# quadcopter.net
KiCad netlist of a schematic drawn in EAGLE
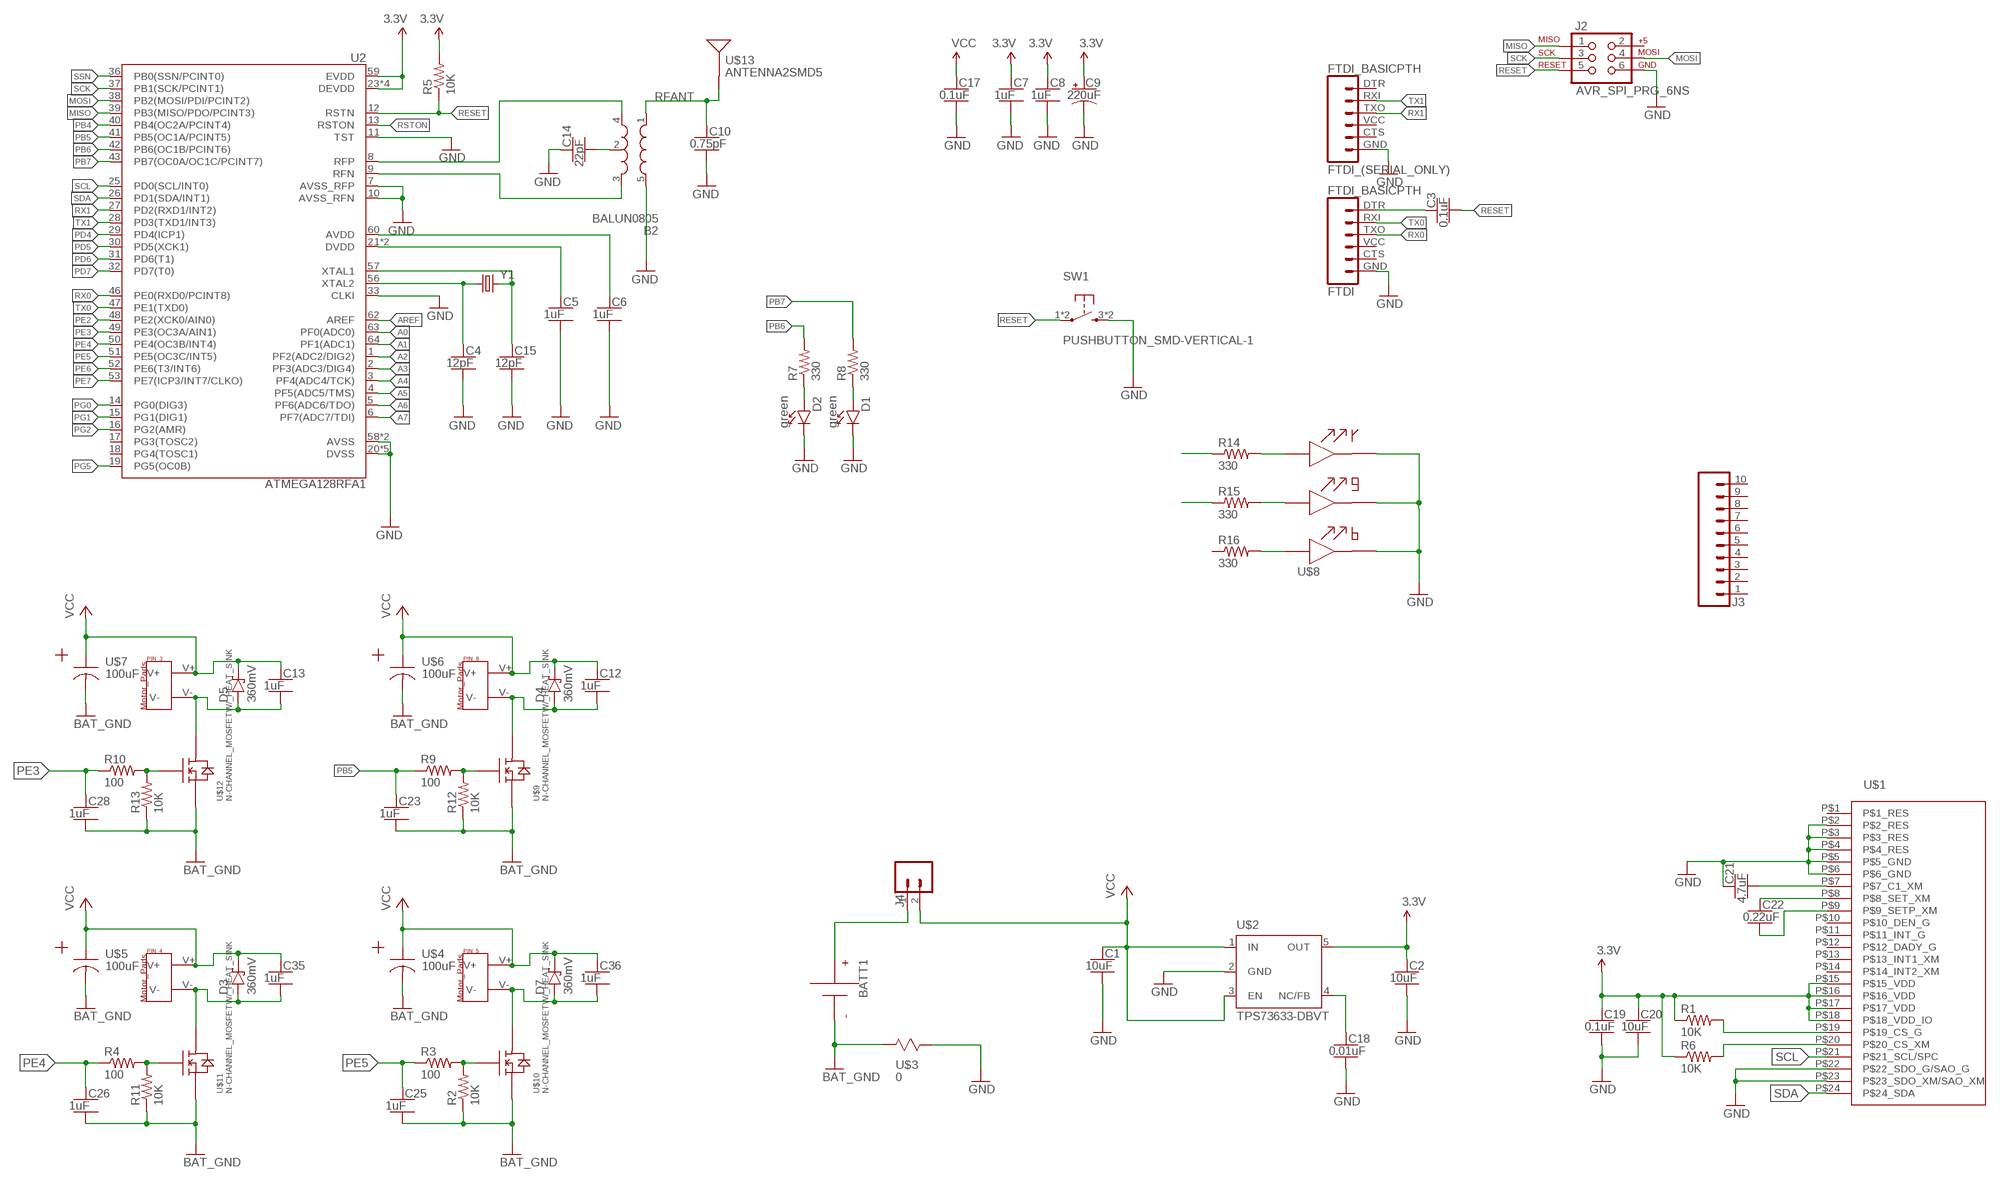
[diagram p0: schematic, sheet 1]

(export (version "E")
  (design (tool "Eeschema 10.0.6"))
  (components
    (comp (ref "B2")
      (value "BALUN0805")
      (footprint "eagle-import:BALUN")
      (fields (field (name "MFR") "Wurth Electronics Inc") (field (name "MPN") "748421245"))
      (libsource (lib "eagle-import") (part "BALUN0805"))
    )
    (comp (ref "BATT1")
      (value "BATTERY-HUBSAN-W/HOLDER")
      (footprint "eagle-import:BATTERY-W_HOLDER-380MAH-HUBSAN")
      (libsource (lib "eagle-import") (part "BATTERY-HUBSAN-W/HOLDER"))
    )
    (comp (ref "C1")
      (value "10uF")
      (footprint "eagle-import:CAPC2012X140_HS")
      (fields
        (field (name "MFR") "Murata Electronics North America")
        (field (name "MPN") "GRM21BR61E106KA73L")
      )
      (libsource (lib "eagle-import") (part "CAPACITOR-NP_SMD-2012-0805_CERAMIC-10UF"))
    )
    (comp (ref "C2")
      (value "10uF")
      (footprint "eagle-import:CAPC2012X140_HS")
      (fields
        (field (name "MFR") "Murata Electronics North America")
        (field (name "MPN") "GRM21BR61E106KA73L")
      )
      (libsource (lib "eagle-import") (part "CAPACITOR-NP_SMD-2012-0805_CERAMIC-10UF"))
    )
    (comp (ref "C3")
      (value "0.1uF")
      (footprint "eagle-import:CAPC2012X140_HS")
      (fields
        (field (name "MFR") "Murata Electronics North America")
        (field (name "MPN") "GRM21BR71H104KA01L")
      )
      (libsource (lib "eagle-import") (part "CAPACITOR-NP_SMD-2012-0805_CERAMIC-0.1UF"))
    )
    (comp (ref "C4")
      (value "12pF")
      (footprint "eagle-import:CAPC2012X140_HS")
      (fields
        (field (name "MFR") "Murata Electronics North America")
        (field (name "MPN") "GRM21A5C2E120JW01D")
      )
      (libsource (lib "eagle-import") (part "CAPACITOR-NP_SMD-2012-0805_CERAMIC-12PF"))
    )
    (comp (ref "C5")
      (value "1uF")
      (footprint "eagle-import:CAPC2012X140_HS")
      (fields
        (field (name "MFR") "Murata Electronics North America")
        (field (name "MPN") "GRM21BR71H105KA12L")
      )
      (libsource (lib "eagle-import") (part "CAPACITOR-NP_SMD-2012-0805_CERAMIC-1UF"))
    )
    (comp (ref "C6")
      (value "1uF")
      (footprint "eagle-import:CAPC2012X140_HS")
      (fields
        (field (name "MFR") "Murata Electronics North America")
        (field (name "MPN") "GRM21BR71H105KA12L")
      )
      (libsource (lib "eagle-import") (part "CAPACITOR-NP_SMD-2012-0805_CERAMIC-1UF"))
    )
    (comp (ref "C7")
      (value "1uF")
      (footprint "eagle-import:CAPC2012X140_HS")
      (fields
        (field (name "MFR") "Murata Electronics North America")
        (field (name "MPN") "GRM21BR71H105KA12L")
      )
      (libsource (lib "eagle-import") (part "CAPACITOR-NP_SMD-2012-0805_CERAMIC-1UF"))
    )
    (comp (ref "C8")
      (value "1uF")
      (footprint "eagle-import:CAPC2012X140_HS")
      (fields
        (field (name "MFR") "Murata Electronics North America")
        (field (name "MPN") "GRM21BR71H105KA12L")
      )
      (libsource (lib "eagle-import") (part "CAPACITOR-NP_SMD-2012-0805_CERAMIC-1UF"))
    )
    (comp (ref "C9")
      (value "220uF")
      (footprint "eagle-import:CAPMP7343X310_HS")
      (fields (field (name "MFR") "AVX Corporation") (field (name "MPN") "TAJD227K006RNJ"))
      (libsource (lib "eagle-import") (part "CAPACITOR-POL_SMD-7043-D_TANTALUM-220UF"))
    )
    (comp (ref "C10")
      (value "0.75pF")
      (footprint "eagle-import:CAPC2012X140_HS")
      (fields
        (field (name "MFR") "Murata Electronics North America")
        (field (name "MPN") "GQM2195C2AR75CB01D")
      )
      (libsource (lib "eagle-import") (part "CAPACITOR-NP_SMD-2012-0805_CERAMIC-0.75PF"))
    )
    (comp (ref "C12")
      (value "1uF")
      (footprint "eagle-import:CAPC2012X140_HS")
      (fields
        (field (name "MFR") "Murata Electronics North America")
        (field (name "MPN") "GRM21BR71H105KA12L")
      )
      (libsource (lib "eagle-import") (part "CAPACITOR-NP_SMD-2012-0805_CERAMIC-1UF"))
    )
    (comp (ref "C13")
      (value "1uF")
      (footprint "eagle-import:CAPC2012X140_HS")
      (fields
        (field (name "MFR") "Murata Electronics North America")
        (field (name "MPN") "GRM21BR71H105KA12L")
      )
      (libsource (lib "eagle-import") (part "CAPACITOR-NP_SMD-2012-0805_CERAMIC-1UF"))
    )
    (comp (ref "C14")
      (value "22pF")
      (footprint "eagle-import:CAPC2012X140_HS")
      (fields
        (field (name "MFR") "Murata Electronics North America")
        (field (name "MPN") "GRM21A5C2E220JW01D")
      )
      (libsource (lib "eagle-import") (part "CAPACITOR-NP_SMD-2012-0805_CERAMIC-22PF"))
    )
    (comp (ref "C15")
      (value "12pF")
      (footprint "eagle-import:CAPC2012X140_HS")
      (fields
        (field (name "MFR") "Murata Electronics North America")
        (field (name "MPN") "GRM21A5C2E120JW01D")
      )
      (libsource (lib "eagle-import") (part "CAPACITOR-NP_SMD-2012-0805_CERAMIC-12PF"))
    )
    (comp (ref "C17")
      (value "0.1uF")
      (footprint "eagle-import:CAPC2012X140_HS")
      (fields
        (field (name "MFR") "Murata Electronics North America")
        (field (name "MPN") "GRM21BR71H104KA01L")
      )
      (libsource (lib "eagle-import") (part "CAPACITOR-NP_SMD-2012-0805_CERAMIC-0.1UF"))
    )
    (comp (ref "C18")
      (value "0.01uF")
      (footprint "eagle-import:CAPC2012X140_HS")
      (fields
        (field (name "MFR") "Murata Electronics North America")
        (field (name "MPN") "GRM2195C1H103FA01D")
      )
      (libsource (lib "eagle-import") (part "CAPACITOR-NP_SMD-2012-0805_CERAMIC-0.01UF"))
    )
    (comp (ref "C19")
      (value "0.1uF")
      (footprint "eagle-import:CAPC2012X140_HS")
      (fields
        (field (name "MFR") "Murata Electronics North America")
        (field (name "MPN") "GRM21BR71H104KA01L")
      )
      (libsource (lib "eagle-import") (part "CAPACITOR-NP_SMD-2012-0805_CERAMIC-0.1UF"))
    )
    (comp (ref "C20")
      (value "10uF")
      (footprint "eagle-import:CAPC2012X140_HS")
      (fields
        (field (name "MFR") "Murata Electronics North America")
        (field (name "MPN") "GRM21BR61E106KA73L")
      )
      (libsource (lib "eagle-import") (part "CAPACITOR-NP_SMD-2012-0805_CERAMIC-10UF"))
    )
    (comp (ref "C21")
      (value "4.7uF")
      (footprint "eagle-import:CAPC2012X140_HS")
      (fields
        (field (name "MFR") "Murata Electronics North America")
        (field (name "MPN") "GRM21BR61E475KA12L")
      )
      (libsource (lib "eagle-import") (part "CAPACITOR-NP_SMD-2012-0805_CERAMIC-4.7UF"))
    )
    (comp (ref "C22")
      (value "0.22uF")
      (footprint "eagle-import:CAPC2012X140_HS")
      (fields
        (field (name "MFR") "Murata Electronics North America")
        (field (name "MPN") "GRM21BR71H224KA01L")
      )
      (libsource (lib "eagle-import") (part "CAPACITOR-NP_SMD-2012-0805_CERAMIC-0.22UF"))
    )
    (comp (ref "C23")
      (value "1uF")
      (footprint "eagle-import:CAPC2012X140_HS")
      (fields
        (field (name "MFR") "Murata Electronics North America")
        (field (name "MPN") "GRM21BR71H105KA12L")
      )
      (libsource (lib "eagle-import") (part "CAPACITOR-NP_SMD-2012-0805_CERAMIC-1UF"))
    )
    (comp (ref "C25")
      (value "1uF")
      (footprint "eagle-import:CAPC2012X140_HS")
      (fields
        (field (name "MFR") "Murata Electronics North America")
        (field (name "MPN") "GRM21BR71H105KA12L")
      )
      (libsource (lib "eagle-import") (part "CAPACITOR-NP_SMD-2012-0805_CERAMIC-1UF"))
    )
    (comp (ref "C26")
      (value "1uF")
      (footprint "eagle-import:CAPC2012X140_HS")
      (fields
        (field (name "MFR") "Murata Electronics North America")
        (field (name "MPN") "GRM21BR71H105KA12L")
      )
      (libsource (lib "eagle-import") (part "CAPACITOR-NP_SMD-2012-0805_CERAMIC-1UF"))
    )
    (comp (ref "C28")
      (value "1uF")
      (footprint "eagle-import:CAPC2012X140_HS")
      (fields
        (field (name "MFR") "Murata Electronics North America")
        (field (name "MPN") "GRM21BR71H105KA12L")
      )
      (libsource (lib "eagle-import") (part "CAPACITOR-NP_SMD-2012-0805_CERAMIC-1UF"))
    )
    (comp (ref "C35")
      (value "1uF")
      (footprint "eagle-import:CAPC2012X140_HS")
      (fields
        (field (name "MFR") "Murata Electronics North America")
        (field (name "MPN") "GRM21BR71H105KA12L")
      )
      (libsource (lib "eagle-import") (part "CAPACITOR-NP_SMD-2012-0805_CERAMIC-1UF"))
    )
    (comp (ref "C36")
      (value "1uF")
      (footprint "eagle-import:CAPC2012X140_HS")
      (fields
        (field (name "MFR") "Murata Electronics North America")
        (field (name "MPN") "GRM21BR71H105KA12L")
      )
      (libsource (lib "eagle-import") (part "CAPACITOR-NP_SMD-2012-0805_CERAMIC-1UF"))
    )
    (comp (ref "D1")
      (value "green")
      (footprint "eagle-import:LEDSC125X200X120-2_HS")
      (fields (field (name "MFR") "Lite-On Inc") (field (name "MPN") "LTST-C170GKT"))
      (libsource (lib "eagle-import") (part "DIODE-LED_SMD-2012-0805-GREEN"))
    )
    (comp (ref "D2")
      (value "green")
      (footprint "eagle-import:LEDSC125X200X120-2_HS")
      (fields (field (name "MFR") "Lite-On Inc") (field (name "MPN") "LTST-C170GKT"))
      (libsource (lib "eagle-import") (part "DIODE-LED_SMD-2012-0805-GREEN"))
    )
    (comp (ref "D3")
      (value "360mV")
      (footprint "eagle-import:SOD3716X135_HS")
      (fields
        (field (name "MFR") "Toshiba Semiconductor and Storage")
        (field (name "MPN") "CRS08(TE85L,Q,M)")
      )
      (libsource (lib "eagle-import") (part "DIODE-SCHOTTKY_SMD-SOD123-360MV"))
    )
    (comp (ref "D4")
      (value "360mV")
      (footprint "eagle-import:SOD3716X135_HS")
      (fields
        (field (name "MFR") "Toshiba Semiconductor and Storage")
        (field (name "MPN") "CRS08(TE85L,Q,M)")
      )
      (libsource (lib "eagle-import") (part "DIODE-SCHOTTKY_SMD-SOD123-360MV"))
    )
    (comp (ref "D5")
      (value "360mV")
      (footprint "eagle-import:SOD3716X135_HS")
      (fields
        (field (name "MFR") "Toshiba Semiconductor and Storage")
        (field (name "MPN") "CRS08(TE85L,Q,M)")
      )
      (libsource (lib "eagle-import") (part "DIODE-SCHOTTKY_SMD-SOD123-360MV"))
    )
    (comp (ref "D7")
      (value "360mV")
      (footprint "eagle-import:SOD3716X135_HS")
      (fields
        (field (name "MFR") "Toshiba Semiconductor and Storage")
        (field (name "MPN") "CRS08(TE85L,Q,M)")
      )
      (libsource (lib "eagle-import") (part "DIODE-SCHOTTKY_SMD-SOD123-360MV"))
    )
    (comp (ref "FTDI")
      (value "FTDI_BASICPTH")
      (footprint "eagle-import:FTDI_BASIC")
      (fields (field (name "MFR") "Amphenol FCI") (field (name "MPN") "68016-406HLF"))
      (libsource (lib "eagle-import") (part "FTDI_BASICPTH"))
    )
    (comp (ref "FTDI_(SERIAL_ONLY)")
      (value "FTDI_BASICPTH")
      (footprint "eagle-import:FTDI_BASIC")
      (fields (field (name "MFR") "Amphenol FCI") (field (name "MPN") "68016-406HLF"))
      (libsource (lib "eagle-import") (part "FTDI_BASICPTH"))
    )
    (comp (ref "J2")
      (value "AVR_SPI_PRG_6NS")
      (footprint "eagle-import:2X3-NS")
      (fields (field (name "MFR") "Amphenol FCI") (field (name "MPN") "67997-206HLF"))
      (libsource (lib "eagle-import") (part "AVR_SPI_PRG_6NS"))
    )
    (comp (ref "J3")
      (value "SIP-10_TH-254X10-1")
      (footprint "eagle-import:HDRV10W63P254_10X1_2540X254H838_HS")
      (fields (field (name "MFR") "Amphenol FCI") (field (name "MPN") "68000-110HLF"))
      (libsource (lib "eagle-import") (part "SIP-10_TH-254X10-1"))
    )
    (comp (ref "J4")
      (value "MALE_HEADER_2POS-2X1-0.1IN")
      (footprint "eagle-import:MALE_HEADER_2X1_0.1IN")
      (fields
        (field (name "MFR") "3M")
        (field (name "MPN") "961102-6404-AR")
        (field (name "CREATOR") "SWANSON")
      )
      (libsource (lib "eagle-import") (part "MALE_HEADER_2POS-2X1-0.1IN"))
    )
    (comp (ref "PIN_3")
      (value "MOTOR_PADS")
      (footprint "eagle-import:MOTOR_PADS")
      (libsource (lib "eagle-import") (part "MOTOR_PADS"))
    )
    (comp (ref "PIN_4")
      (value "MOTOR_PADS")
      (footprint "eagle-import:MOTOR_PADS")
      (libsource (lib "eagle-import") (part "MOTOR_PADS"))
    )
    (comp (ref "PIN_5")
      (value "MOTOR_PADS")
      (footprint "eagle-import:MOTOR_PADS")
      (libsource (lib "eagle-import") (part "MOTOR_PADS"))
    )
    (comp (ref "PIN_8")
      (value "MOTOR_PADS")
      (footprint "eagle-import:MOTOR_PADS")
      (libsource (lib "eagle-import") (part "MOTOR_PADS"))
    )
    (comp (ref "R1")
      (value "10K")
      (footprint "eagle-import:RESC2012X60_HS")
      (fields (field (name "MFR") "Yageo") (field (name "MPN") "RC0805JR-0710KL"))
      (libsource (lib "eagle-import") (part "RESISTOR_SMD-2012-0805-10K"))
    )
    (comp (ref "R2")
      (value "10K")
      (footprint "eagle-import:RESC2012X60_HS")
      (fields (field (name "MFR") "Yageo") (field (name "MPN") "RC0805JR-0710KL"))
      (libsource (lib "eagle-import") (part "RESISTOR_SMD-2012-0805-10K"))
    )
    (comp (ref "R3")
      (value "100")
      (footprint "eagle-import:RESC2012X60_HS")
      (fields (field (name "MFR") "Yageo") (field (name "MPN") "RC0805JR-07100RL"))
      (libsource (lib "eagle-import") (part "RESISTOR_SMD-2012-0805-100"))
    )
    (comp (ref "R4")
      (value "100")
      (footprint "eagle-import:RESC2012X60_HS")
      (fields (field (name "MFR") "Yageo") (field (name "MPN") "RC0805JR-07100RL"))
      (libsource (lib "eagle-import") (part "RESISTOR_SMD-2012-0805-100"))
    )
    (comp (ref "R5")
      (value "10K")
      (footprint "eagle-import:RESC2012X60_HS")
      (fields (field (name "MFR") "Yageo") (field (name "MPN") "RC0805JR-0710KL"))
      (libsource (lib "eagle-import") (part "RESISTOR_SMD-2012-0805-10K"))
    )
    (comp (ref "R6")
      (value "10K")
      (footprint "eagle-import:RESC2012X60_HS")
      (fields (field (name "MFR") "Yageo") (field (name "MPN") "RC0805JR-0710KL"))
      (libsource (lib "eagle-import") (part "RESISTOR_SMD-2012-0805-10K"))
    )
    (comp (ref "R7")
      (value "330")
      (footprint "eagle-import:RESC2012X60_HS")
      (fields (field (name "MFR") "Yageo") (field (name "MPN") "RC0805JR-07330RL"))
      (libsource (lib "eagle-import") (part "RESISTOR_SMD-2012-0805-330"))
    )
    (comp (ref "R8")
      (value "330")
      (footprint "eagle-import:RESC2012X60_HS")
      (fields (field (name "MFR") "Yageo") (field (name "MPN") "RC0805JR-07330RL"))
      (libsource (lib "eagle-import") (part "RESISTOR_SMD-2012-0805-330"))
    )
    (comp (ref "R9")
      (value "100")
      (footprint "eagle-import:RESC2012X60_HS")
      (fields (field (name "MFR") "Yageo") (field (name "MPN") "RC0805JR-07100RL"))
      (libsource (lib "eagle-import") (part "RESISTOR_SMD-2012-0805-100"))
    )
    (comp (ref "R10")
      (value "100")
      (footprint "eagle-import:RESC2012X60_HS")
      (fields (field (name "MFR") "Yageo") (field (name "MPN") "RC0805JR-07100RL"))
      (libsource (lib "eagle-import") (part "RESISTOR_SMD-2012-0805-100"))
    )
    (comp (ref "R11")
      (value "10K")
      (footprint "eagle-import:RESC2012X60_HS")
      (fields (field (name "MFR") "Yageo") (field (name "MPN") "RC0805JR-0710KL"))
      (libsource (lib "eagle-import") (part "RESISTOR_SMD-2012-0805-10K"))
    )
    (comp (ref "R12")
      (value "10K")
      (footprint "eagle-import:RESC2012X60_HS")
      (fields (field (name "MFR") "Yageo") (field (name "MPN") "RC0805JR-0710KL"))
      (libsource (lib "eagle-import") (part "RESISTOR_SMD-2012-0805-10K"))
    )
    (comp (ref "R13")
      (value "10K")
      (footprint "eagle-import:RESC2012X60_HS")
      (fields (field (name "MFR") "Yageo") (field (name "MPN") "RC0805JR-0710KL"))
      (libsource (lib "eagle-import") (part "RESISTOR_SMD-2012-0805-10K"))
    )
    (comp (ref "R14")
      (value "330")
      (footprint "eagle-import:RESC2012X60_HS")
      (fields (field (name "MFR") "Yageo") (field (name "MPN") "RC0805JR-07330RL"))
      (libsource (lib "eagle-import") (part "RESISTOR_SMD-2012-0805-330"))
    )
    (comp (ref "R15")
      (value "330")
      (footprint "eagle-import:RESC2012X60_HS")
      (fields (field (name "MFR") "Yageo") (field (name "MPN") "RC0805JR-07330RL"))
      (libsource (lib "eagle-import") (part "RESISTOR_SMD-2012-0805-330"))
    )
    (comp (ref "R16")
      (value "330")
      (footprint "eagle-import:RESC2012X60_HS")
      (fields (field (name "MFR") "Yageo") (field (name "MPN") "RC0805JR-07330RL"))
      (libsource (lib "eagle-import") (part "RESISTOR_SMD-2012-0805-330"))
    )
    (comp (ref "SW1")
      (value "PUSHBUTTON_SMD-VERTICAL-1")
      (footprint "eagle-import:TE_FSM8JSMA_HS")
      (fields (field (name "MFR") "TE Connectivity Alcoswitch Switches") (field (name "MPN") "FSM4JSMA"))
      (libsource (lib "eagle-import") (part "PUSHBUTTON_SMD-VERTICAL-1"))
    )
    (comp (ref "U$1")
      (value "IMU")
      (footprint "eagle-import:LGA-24_4X4MM")
      (fields (field (name "MFR") "STMicroelectronics") (field (name "CREATOR") "Xuefei"))
      (libsource (lib "eagle-import") (part "IMU"))
    )
    (comp (ref "U$2")
      (value "TPS73633-DBVT")
      (footprint "eagle-import:SOT23-DBV")
      (fields (field (name "MFR") "Texas Instruments") (field (name "MPN") "LP3985IM5X-3.0/NOPB"))
      (libsource (lib "eagle-import") (part "TPS73633-DBVT"))
    )
    (comp (ref "U$3")
      (value "0")
      (footprint "eagle-import:SMD_RESISTOR")
      (fields
        (field (name "MFR") "Yageo")
        (field (name "MPN") "RC0805JR-070RL")
        (field (name "CREATOR") "Xuefei")
      )
      (libsource (lib "eagle-import") (part "RESISTOR"))
    )
    (comp (ref "U$4")
      (value "100uF")
      (footprint "eagle-import:TAJB_SMB_POLAR_CAP")
      (fields
        (field (name "MFR") "AVX Corporation")
        (field (name "MPN") "TAJB107K006RNJ")
        (field (name "CREATOR") "Xuefei")
      )
      (libsource (lib "eagle-import") (part "POLAR_CAP"))
    )
    (comp (ref "U$5")
      (value "100uF")
      (footprint "eagle-import:TAJB_SMB_POLAR_CAP")
      (fields
        (field (name "MFR") "AVX Corporation")
        (field (name "MPN") "TAJB107K006RNJ")
        (field (name "CREATOR") "Xuefei")
      )
      (libsource (lib "eagle-import") (part "POLAR_CAP"))
    )
    (comp (ref "U$6")
      (value "100uF")
      (footprint "eagle-import:TAJB_SMB_POLAR_CAP")
      (fields
        (field (name "MFR") "AVX Corporation")
        (field (name "MPN") "TAJB107K006RNJ")
        (field (name "CREATOR") "Xuefei")
      )
      (libsource (lib "eagle-import") (part "POLAR_CAP"))
    )
    (comp (ref "U$7")
      (value "100uF")
      (footprint "eagle-import:TAJB_SMB_POLAR_CAP")
      (fields
        (field (name "MFR") "AVX Corporation")
        (field (name "MPN") "TAJB107K006RNJ")
        (field (name "CREATOR") "Xuefei")
      )
      (libsource (lib "eagle-import") (part "POLAR_CAP"))
    )
    (comp (ref "U$8")
      (value "QBLP679E-RGB")
      (footprint "eagle-import:QBLP679E-RGB")
      (fields (field (name "MFR") "QT Brightek (QTB)") (field (name "CREATOR") "Xuefei"))
      (libsource (lib "eagle-import") (part "QBLP679E-RGB"))
    )
    (comp (ref "U$9")
      (value "N-CHANNEL_MOSFETW/_HEAT_SINK")
      (footprint "eagle-import:LITTLE_FOOT_MOSFET_W__HEAT_SPREADER")
      (libsource (lib "eagle-import") (part "N-CHANNEL_MOSFETW/_HEAT_SINK"))
    )
    (comp (ref "U$10")
      (value "N-CHANNEL_MOSFETW/_HEAT_SINK")
      (footprint "eagle-import:LITTLE_FOOT_MOSFET_W__HEAT_SPREADER")
      (libsource (lib "eagle-import") (part "N-CHANNEL_MOSFETW/_HEAT_SINK"))
    )
    (comp (ref "U$11")
      (value "N-CHANNEL_MOSFETW/_HEAT_SINK")
      (footprint "eagle-import:LITTLE_FOOT_MOSFET_W__HEAT_SPREADER")
      (libsource (lib "eagle-import") (part "N-CHANNEL_MOSFETW/_HEAT_SINK"))
    )
    (comp (ref "U$12")
      (value "N-CHANNEL_MOSFETW/_HEAT_SINK")
      (footprint "eagle-import:LITTLE_FOOT_MOSFET_W__HEAT_SPREADER")
      (libsource (lib "eagle-import") (part "N-CHANNEL_MOSFETW/_HEAT_SINK"))
    )
    (comp (ref "U$13")
      (value "ANTENNA2SMD5")
      (footprint "eagle-import:ANTENNA-CHIP5")
      (fields (field (name "MFR") "Linx Technologies Inc.") (field (name "MPN") "ANT-2.45-CHP-T"))
      (libsource (lib "eagle-import") (part "ANTENNA2SMD5"))
    )
    (comp (ref "U2")
      (value "ATMEGA128RFA1")
      (footprint "eagle-import:QFN-64")
      (fields (field (name "MFR") "Atmel") (field (name "MPN") "ATMEGA128RFA1-ZUR00"))
      (libsource (lib "eagle-import") (part "ATMEGA128RFA1"))
    )
    (comp (ref "Y1")
      (value "CRYSTAL5X3")
      (footprint "eagle-import:CRYSTAL-SMD-5X3")
      (fields (field (name "MFR") "Abracon LLC") (field (name "MPN") "ABM3B-16.000MHZ-B2-T"))
      (libsource (lib "eagle-import") (part "CRYSTAL5X3"))
    )
  )
  (nets
    (net (code "1") (name "/RFANT") (class "Default")
      (node (ref "B2") (pin "1") (pinfunction "IN_1") (pintype "bidirectional"))
      (node (ref "C10") (pin "1") (pinfunction "1_1") (pintype "passive"))
      (node (ref "U$13") (pin "FEED") (pinfunction "SIGNAL_FEED") (pintype "bidirectional"))
    )
    (net (code "2") (name "3.3V") (class "Default")
      (node (ref "C19") (pin "1") (pinfunction "1_1") (pintype "passive"))
      (node (ref "C2") (pin "1") (pinfunction "1_1") (pintype "passive"))
      (node (ref "C20") (pin "1") (pinfunction "1_1") (pintype "passive"))
      (node (ref "C7") (pin "1") (pinfunction "1_1") (pintype "passive"))
      (node (ref "C8") (pin "1") (pinfunction "1_1") (pintype "passive"))
      (node (ref "C9") (pin "1") (pinfunction "+_1") (pintype "passive"))
      (node (ref "R1") (pin "1") (pinfunction "1_1") (pintype "passive"))
      (node (ref "R5") (pin "2") (pinfunction "2_2") (pintype "passive"))
      (node (ref "R6") (pin "1") (pinfunction "1_1") (pintype "passive"))
      (node (ref "U$1") (pin "P$15") (pinfunction "P$15_VDD_P$15") (pintype "bidirectional"))
      (node (ref "U$1") (pin "P$16") (pinfunction "P$16_VDD_P$16") (pintype "bidirectional"))
      (node (ref "U$1") (pin "P$17") (pinfunction "P$17_VDD_P$17") (pintype "bidirectional"))
      (node (ref "U$1") (pin "P$18") (pinfunction "P$18_VDD_IO_P$18") (pintype "bidirectional"))
      (node (ref "U$2") (pin "5") (pinfunction "OUT_5") (pintype "passive"))
      (node (ref "U2") (pin "23") (pinfunction "DEVDD_23") (pintype "bidirectional"))
      (node (ref "U2") (pin "34") (pinfunction "DEVDD_34") (pintype "bidirectional"))
      (node (ref "U2") (pin "44") (pinfunction "DEVDD_44") (pintype "bidirectional"))
      (node (ref "U2") (pin "54") (pinfunction "DEVDD_54") (pintype "bidirectional"))
      (node (ref "U2") (pin "59") (pinfunction "EVDD_59") (pintype "bidirectional"))
    )
    (net (code "3") (name "A0") (class "Default")
      (node (ref "U2") (pin "63") (pinfunction "PF0(ADC0)_63") (pintype "bidirectional"))
    )
    (net (code "4") (name "A1") (class "Default")
      (node (ref "U2") (pin "64") (pinfunction "PF1(ADC1)_64") (pintype "bidirectional"))
    )
    (net (code "5") (name "A2") (class "Default")
      (node (ref "U2") (pin "1") (pinfunction "PF2(ADC2/DIG2)_1") (pintype "bidirectional"))
    )
    (net (code "6") (name "A3") (class "Default")
      (node (ref "U2") (pin "2") (pinfunction "PF3(ADC3/DIG4)_2") (pintype "bidirectional"))
    )
    (net (code "7") (name "A4") (class "Default")
      (node (ref "U2") (pin "3") (pinfunction "PF4(ADC4/TCK)_3") (pintype "bidirectional"))
    )
    (net (code "8") (name "A5") (class "Default")
      (node (ref "U2") (pin "4") (pinfunction "PF5(ADC5/TMS)_4") (pintype "bidirectional"))
    )
    (net (code "9") (name "A6") (class "Default")
      (node (ref "U2") (pin "5") (pinfunction "PF6(ADC6/TDO)_5") (pintype "bidirectional"))
    )
    (net (code "10") (name "A7") (class "Default")
      (node (ref "U2") (pin "6") (pinfunction "PF7(ADC7/TDI)_6") (pintype "bidirectional"))
    )
    (net (code "11") (name "AREF") (class "Default")
      (node (ref "U2") (pin "62") (pinfunction "AREF_62") (pintype "bidirectional"))
    )
    (net (code "12") (name "BAT_GND") (class "Default")
      (node (ref "BATT1") (pin "-") (pinfunction "N_-") (pintype "bidirectional"))
      (node (ref "C23") (pin "2") (pinfunction "2_2") (pintype "passive"))
      (node (ref "C25") (pin "2") (pinfunction "2_2") (pintype "passive"))
      (node (ref "C26") (pin "2") (pinfunction "2_2") (pintype "passive"))
      (node (ref "C28") (pin "2") (pinfunction "2_2") (pintype "passive"))
      (node (ref "R11") (pin "1") (pinfunction "1_1") (pintype "passive"))
      (node (ref "R12") (pin "1") (pinfunction "1_1") (pintype "passive"))
      (node (ref "R13") (pin "1") (pinfunction "1_1") (pintype "passive"))
      (node (ref "R2") (pin "1") (pinfunction "1_1") (pintype "passive"))
      (node (ref "U$10") (pin "P$2") (pinfunction "P$2_S_P$2") (pintype "bidirectional"))
      (node (ref "U$11") (pin "P$2") (pinfunction "P$2_S_P$2") (pintype "bidirectional"))
      (node (ref "U$12") (pin "P$2") (pinfunction "P$2_S_P$2") (pintype "bidirectional"))
      (node (ref "U$3") (pin "P$1") (pinfunction "P$1_P$1") (pintype "bidirectional"))
      (node (ref "U$4") (pin "P$2") (pinfunction "2_P$2") (pintype "passive"))
      (node (ref "U$5") (pin "P$2") (pinfunction "2_P$2") (pintype "passive"))
      (node (ref "U$6") (pin "P$2") (pinfunction "2_P$2") (pintype "passive"))
      (node (ref "U$7") (pin "P$2") (pinfunction "2_P$2") (pintype "passive"))
      (node (ref "U$9") (pin "P$2") (pinfunction "P$2_S_P$2") (pintype "bidirectional"))
    )
    (net (code "13") (name "GND") (class "Default")
      (node (ref "B2") (pin "5") (pinfunction "GND_5") (pintype "bidirectional"))
      (node (ref "C1") (pin "2") (pinfunction "2_2") (pintype "passive"))
      (node (ref "C10") (pin "2") (pinfunction "2_2") (pintype "passive"))
      (node (ref "C14") (pin "1") (pinfunction "1_1") (pintype "passive"))
      (node (ref "C15") (pin "2") (pinfunction "2_2") (pintype "passive"))
      (node (ref "C17") (pin "2") (pinfunction "2_2") (pintype "passive"))
      (node (ref "C18") (pin "2") (pinfunction "2_2") (pintype "passive"))
      (node (ref "C19") (pin "2") (pinfunction "2_2") (pintype "passive"))
      (node (ref "C2") (pin "2") (pinfunction "2_2") (pintype "passive"))
      (node (ref "C20") (pin "2") (pinfunction "2_2") (pintype "passive"))
      (node (ref "C21") (pin "1") (pinfunction "1_1") (pintype "passive"))
      (node (ref "C4") (pin "2") (pinfunction "2_2") (pintype "passive"))
      (node (ref "C5") (pin "2") (pinfunction "2_2") (pintype "passive"))
      (node (ref "C6") (pin "2") (pinfunction "2_2") (pintype "passive"))
      (node (ref "C7") (pin "2") (pinfunction "2_2") (pintype "passive"))
      (node (ref "C8") (pin "2") (pinfunction "2_2") (pintype "passive"))
      (node (ref "C9") (pin "2") (pinfunction "-_2") (pintype "passive"))
      (node (ref "D1") (pin "C") (pinfunction "C_C") (pintype "passive"))
      (node (ref "D2") (pin "C") (pinfunction "C_C") (pintype "passive"))
      (node (ref "FTDI") (pin "GND") (pinfunction "6_GND") (pintype "passive"))
      (node (ref "FTDI_(SERIAL_ONLY)") (pin "GND") (pinfunction "6_GND") (pintype "passive"))
      (node (ref "J2") (pin "6") (pinfunction "6_6") (pintype "passive"))
      (node (ref "SW1") (pin "3") (pinfunction "2_3") (pintype "passive"))
      (node (ref "SW1") (pin "4") (pinfunction "2_4") (pintype "passive"))
      (node (ref "U$1") (pin "P$2") (pinfunction "P$2_RES_P$2") (pintype "bidirectional"))
      (node (ref "U$1") (pin "P$22") (pinfunction "P$22_SDO_G/SAO_G_P$22") (pintype "bidirectional"))
      (node (ref "U$1") (pin "P$23") (pinfunction "P$23_SDO_XM/SAO_XM_P$23") (pintype "bidirectional"))
      (node (ref "U$1") (pin "P$3") (pinfunction "P$3_RES_P$3") (pintype "bidirectional"))
      (node (ref "U$1") (pin "P$4") (pinfunction "P$4_RES_P$4") (pintype "bidirectional"))
      (node (ref "U$1") (pin "P$5") (pinfunction "P$5_GND_P$5") (pintype "bidirectional"))
      (node (ref "U$1") (pin "P$6") (pinfunction "P$6_GND_P$6") (pintype "bidirectional"))
      (node (ref "U$2") (pin "2") (pinfunction "GND_2") (pintype "input"))
      (node (ref "U$3") (pin "P$2") (pinfunction "P$2_P$2") (pintype "bidirectional"))
      (node (ref "U$8") (pin "P$1") (pinfunction "P$1_P$1") (pintype "bidirectional"))
      (node (ref "U$8") (pin "P$2") (pinfunction "P$2_P$2") (pintype "bidirectional"))
      (node (ref "U$8") (pin "P$3") (pinfunction "P$3_P$3") (pintype "bidirectional"))
      (node (ref "U2") (pin "10") (pinfunction "AVSS_RFN_10") (pintype "bidirectional"))
      (node (ref "U2") (pin "11") (pinfunction "TST_11") (pintype "bidirectional"))
      (node (ref "U2") (pin "20") (pinfunction "DVSS_20") (pintype "bidirectional"))
      (node (ref "U2") (pin "24") (pinfunction "DVSS_24") (pintype "bidirectional"))
      (node (ref "U2") (pin "33") (pinfunction "CLKI_33") (pintype "bidirectional"))
      (node (ref "U2") (pin "35") (pinfunction "DVSS_35") (pintype "bidirectional"))
      (node (ref "U2") (pin "45") (pinfunction "DVSS_45") (pintype "bidirectional"))
      (node (ref "U2") (pin "55") (pinfunction "DVSS_55") (pintype "bidirectional"))
      (node (ref "U2") (pin "58") (pinfunction "AVSS_58") (pintype "bidirectional"))
      (node (ref "U2") (pin "61") (pinfunction "AVSS_61") (pintype "bidirectional"))
      (node (ref "U2") (pin "7") (pinfunction "AVSS_RFP_7") (pintype "bidirectional"))
    )
    (net (code "14") (name "MISO") (class "Default")
      (node (ref "J2") (pin "1") (pinfunction "1_1") (pintype "passive"))
      (node (ref "U2") (pin "39") (pinfunction "PB3(MISO/PDO/PCINT3)_39") (pintype "bidirectional"))
    )
    (net (code "15") (name "MOSI") (class "Default")
      (node (ref "J2") (pin "4") (pinfunction "4_4") (pintype "passive"))
      (node (ref "U2") (pin "38") (pinfunction "PB2(MOSI/PDI/PCINT2)_38") (pintype "bidirectional"))
    )
    (net (code "16") (name "Net-(B2-GND-Pad2)") (class "Default")
      (node (ref "B2") (pin "2") (pinfunction "GND_2") (pintype "bidirectional"))
      (node (ref "C14") (pin "2") (pinfunction "2_2") (pintype "passive"))
    )
    (net (code "17") (name "Net-(B2-OUT1)") (class "Default")
      (node (ref "B2") (pin "4") (pinfunction "OUT1_4") (pintype "bidirectional"))
      (node (ref "U2") (pin "8") (pinfunction "RFP_8") (pintype "bidirectional"))
    )
    (net (code "18") (name "Net-(B2-OUT2)") (class "Default")
      (node (ref "B2") (pin "3") (pinfunction "OUT2_3") (pintype "bidirectional"))
      (node (ref "U2") (pin "9") (pinfunction "RFN_9") (pintype "bidirectional"))
    )
    (net (code "19") (name "Net-(BATT1-P)") (class "Default")
      (node (ref "BATT1") (pin "+") (pinfunction "P_+") (pintype "bidirectional"))
      (node (ref "J4") (pin "1") (pinfunction "1_1") (pintype "passive"))
    )
    (net (code "20") (name "Net-(C5-Pad1)") (class "Default")
      (node (ref "C5") (pin "1") (pinfunction "1_1") (pintype "passive"))
      (node (ref "U2") (pin "21") (pinfunction "DVDD_21") (pintype "bidirectional"))
      (node (ref "U2") (pin "22") (pinfunction "DVDD_22") (pintype "bidirectional"))
    )
    (net (code "21") (name "Net-(D1-PadA)") (class "Default")
      (node (ref "D1") (pin "A") (pinfunction "A_A") (pintype "passive"))
      (node (ref "R8") (pin "1") (pinfunction "1_1") (pintype "passive"))
    )
    (net (code "22") (name "Net-(D2-PadA)") (class "Default")
      (node (ref "D2") (pin "A") (pinfunction "A_A") (pintype "passive"))
      (node (ref "R7") (pin "1") (pinfunction "1_1") (pintype "passive"))
    )
    (net (code "23") (name "Net-(FTDI-1)") (class "Default")
      (node (ref "C3") (pin "1") (pinfunction "1_1") (pintype "passive"))
      (node (ref "FTDI") (pin "DTR") (pinfunction "1_DTR") (pintype "passive"))
    )
    (net (code "24") (name "Net-(R14-Pad2)") (class "Default")
      (node (ref "R14") (pin "2") (pinfunction "2_2") (pintype "passive"))
      (node (ref "U$8") (pin "P$4") (pinfunction "P$4_P$4") (pintype "bidirectional"))
    )
    (net (code "25") (name "Net-(R15-Pad2)") (class "Default")
      (node (ref "R15") (pin "2") (pinfunction "2_2") (pintype "passive"))
      (node (ref "U$8") (pin "P$5") (pinfunction "P$5_P$5") (pintype "bidirectional"))
    )
    (net (code "26") (name "Net-(R16-Pad2)") (class "Default")
      (node (ref "R16") (pin "2") (pinfunction "2_2") (pintype "passive"))
      (node (ref "U$8") (pin "P$6") (pinfunction "P$6_P$6") (pintype "bidirectional"))
    )
    (net (code "27") (name "Net-(U$1-P$7_C1_XM)") (class "Default")
      (node (ref "C21") (pin "2") (pinfunction "2_2") (pintype "passive"))
      (node (ref "U$1") (pin "P$7") (pinfunction "P$7_C1_XM_P$7") (pintype "bidirectional"))
    )
    (net (code "28") (name "Net-(U$1-P$8_SET_XM)") (class "Default")
      (node (ref "C22") (pin "1") (pinfunction "1_1") (pintype "passive"))
      (node (ref "U$1") (pin "P$8") (pinfunction "P$8_SET_XM_P$8") (pintype "bidirectional"))
    )
    (net (code "29") (name "Net-(U$1-P$9_SETP_XM)") (class "Default")
      (node (ref "C22") (pin "2") (pinfunction "2_2") (pintype "passive"))
      (node (ref "U$1") (pin "P$9") (pinfunction "P$9_SETP_XM_P$9") (pintype "bidirectional"))
    )
    (net (code "30") (name "Net-(U$1-P$19_CS_G)") (class "Default")
      (node (ref "R1") (pin "2") (pinfunction "2_2") (pintype "passive"))
      (node (ref "U$1") (pin "P$19") (pinfunction "P$19_CS_G_P$19") (pintype "bidirectional"))
    )
    (net (code "31") (name "Net-(U$1-P$20_CS_XM)") (class "Default")
      (node (ref "R6") (pin "2") (pinfunction "2_2") (pintype "passive"))
      (node (ref "U$1") (pin "P$20") (pinfunction "P$20_CS_XM_P$20") (pintype "bidirectional"))
    )
    (net (code "32") (name "Net-(U$2-NC{slash}FB)") (class "Default")
      (node (ref "C18") (pin "1") (pinfunction "1_1") (pintype "passive"))
      (node (ref "U$2") (pin "4") (pinfunction "NC/FB_4") (pintype "passive"))
    )
    (net (code "33") (name "Net-(U$9-P$1_G)") (class "Default")
      (node (ref "R12") (pin "2") (pinfunction "2_2") (pintype "passive"))
      (node (ref "R9") (pin "2") (pinfunction "2_2") (pintype "passive"))
      (node (ref "U$9") (pin "P$1") (pinfunction "P$1_G_P$1") (pintype "bidirectional"))
    )
    (net (code "34") (name "Net-(U$9-P$3_D)") (class "Default")
      (node (ref "C12") (pin "2") (pinfunction "2_2") (pintype "passive"))
      (node (ref "D4") (pin "A") (pinfunction "A_A") (pintype "passive"))
      (node (ref "PIN_8") (pin "V-") (pinfunction "V-_V-") (pintype "bidirectional"))
      (node (ref "U$9") (pin "P$3") (pinfunction "P$3_D_P$3") (pintype "bidirectional"))
    )
    (net (code "35") (name "Net-(U$10-P$1_G)") (class "Default")
      (node (ref "R2") (pin "2") (pinfunction "2_2") (pintype "passive"))
      (node (ref "R3") (pin "2") (pinfunction "2_2") (pintype "passive"))
      (node (ref "U$10") (pin "P$1") (pinfunction "P$1_G_P$1") (pintype "bidirectional"))
    )
    (net (code "36") (name "Net-(U$10-P$3_D)") (class "Default")
      (node (ref "C36") (pin "2") (pinfunction "2_2") (pintype "passive"))
      (node (ref "D7") (pin "A") (pinfunction "A_A") (pintype "passive"))
      (node (ref "PIN_5") (pin "V-") (pinfunction "V-_V-") (pintype "bidirectional"))
      (node (ref "U$10") (pin "P$3") (pinfunction "P$3_D_P$3") (pintype "bidirectional"))
    )
    (net (code "37") (name "Net-(U$11-P$1_G)") (class "Default")
      (node (ref "R11") (pin "2") (pinfunction "2_2") (pintype "passive"))
      (node (ref "R4") (pin "2") (pinfunction "2_2") (pintype "passive"))
      (node (ref "U$11") (pin "P$1") (pinfunction "P$1_G_P$1") (pintype "bidirectional"))
    )
    (net (code "38") (name "Net-(U$11-P$3_D)") (class "Default")
      (node (ref "C35") (pin "2") (pinfunction "2_2") (pintype "passive"))
      (node (ref "D3") (pin "A") (pinfunction "A_A") (pintype "passive"))
      (node (ref "PIN_4") (pin "V-") (pinfunction "V-_V-") (pintype "bidirectional"))
      (node (ref "U$11") (pin "P$3") (pinfunction "P$3_D_P$3") (pintype "bidirectional"))
    )
    (net (code "39") (name "Net-(U$12-P$1_G)") (class "Default")
      (node (ref "R10") (pin "2") (pinfunction "2_2") (pintype "passive"))
      (node (ref "R13") (pin "2") (pinfunction "2_2") (pintype "passive"))
      (node (ref "U$12") (pin "P$1") (pinfunction "P$1_G_P$1") (pintype "bidirectional"))
    )
    (net (code "40") (name "Net-(U$12-P$3_D)") (class "Default")
      (node (ref "C13") (pin "2") (pinfunction "2_2") (pintype "passive"))
      (node (ref "D5") (pin "A") (pinfunction "A_A") (pintype "passive"))
      (node (ref "PIN_3") (pin "V-") (pinfunction "V-_V-") (pintype "bidirectional"))
      (node (ref "U$12") (pin "P$3") (pinfunction "P$3_D_P$3") (pintype "bidirectional"))
    )
    (net (code "41") (name "Net-(U2-AVDD)") (class "Default")
      (node (ref "C6") (pin "1") (pinfunction "1_1") (pintype "passive"))
      (node (ref "U2") (pin "60") (pinfunction "AVDD_60") (pintype "bidirectional"))
    )
    (net (code "42") (name "Net-(U2-XTAL1)") (class "Default")
      (node (ref "C15") (pin "1") (pinfunction "1_1") (pintype "passive"))
      (node (ref "U2") (pin "57") (pinfunction "XTAL1_57") (pintype "bidirectional"))
      (node (ref "Y1") (pin "3") (pinfunction "2_3") (pintype "passive"))
    )
    (net (code "43") (name "Net-(U2-XTAL2)") (class "Default")
      (node (ref "C4") (pin "1") (pinfunction "1_1") (pintype "passive"))
      (node (ref "U2") (pin "56") (pinfunction "XTAL2_56") (pintype "bidirectional"))
      (node (ref "Y1") (pin "1") (pinfunction "1_1") (pintype "passive"))
    )
    (net (code "44") (name "PB4") (class "Default")
      (node (ref "R14") (pin "1") (pinfunction "1_1") (pintype "passive"))
      (node (ref "U2") (pin "40") (pinfunction "PB4(OC2A/PCINT4)_40") (pintype "bidirectional"))
    )
    (net (code "45") (name "PB5") (class "Default")
      (node (ref "C23") (pin "1") (pinfunction "1_1") (pintype "passive"))
      (node (ref "R9") (pin "1") (pinfunction "1_1") (pintype "passive"))
      (node (ref "U2") (pin "41") (pinfunction "PB5(OC1A/PCINT5)_41") (pintype "bidirectional"))
    )
    (net (code "46") (name "PB6") (class "Default")
      (node (ref "R7") (pin "2") (pinfunction "2_2") (pintype "passive"))
      (node (ref "U2") (pin "42") (pinfunction "PB6(OC1B/PCINT6)_42") (pintype "bidirectional"))
    )
    (net (code "47") (name "PB7") (class "Default")
      (node (ref "R8") (pin "2") (pinfunction "2_2") (pintype "passive"))
      (node (ref "U2") (pin "43") (pinfunction "PB7(OC0A/OC1C/PCINT7)_43") (pintype "bidirectional"))
    )
    (net (code "48") (name "PD4") (class "Default")
      (node (ref "U2") (pin "29") (pinfunction "PD4(ICP1)_29") (pintype "bidirectional"))
    )
    (net (code "49") (name "PD5") (class "Default")
      (node (ref "U2") (pin "30") (pinfunction "PD5(XCK1)_30") (pintype "bidirectional"))
    )
    (net (code "50") (name "PD6") (class "Default")
      (node (ref "U2") (pin "31") (pinfunction "PD6(T1)_31") (pintype "bidirectional"))
    )
    (net (code "51") (name "PD7") (class "Default")
      (node (ref "U2") (pin "32") (pinfunction "PD7(T0)_32") (pintype "bidirectional"))
    )
    (net (code "52") (name "PE2") (class "Default")
      (node (ref "U2") (pin "48") (pinfunction "PE2(XCK0/AIN0)_48") (pintype "bidirectional"))
    )
    (net (code "53") (name "PE3") (class "Default")
      (node (ref "C28") (pin "1") (pinfunction "1_1") (pintype "passive"))
      (node (ref "R10") (pin "1") (pinfunction "1_1") (pintype "passive"))
      (node (ref "U2") (pin "49") (pinfunction "PE3(OC3A/AIN1)_49") (pintype "bidirectional"))
    )
    (net (code "54") (name "PE4") (class "Default")
      (node (ref "C26") (pin "1") (pinfunction "1_1") (pintype "passive"))
      (node (ref "R4") (pin "1") (pinfunction "1_1") (pintype "passive"))
      (node (ref "U2") (pin "50") (pinfunction "PE4(OC3B/INT4)_50") (pintype "bidirectional"))
    )
    (net (code "55") (name "PE5") (class "Default")
      (node (ref "C25") (pin "1") (pinfunction "1_1") (pintype "passive"))
      (node (ref "R3") (pin "1") (pinfunction "1_1") (pintype "passive"))
      (node (ref "U2") (pin "51") (pinfunction "PE5(OC3C/INT5)_51") (pintype "bidirectional"))
    )
    (net (code "56") (name "PE6") (class "Default")
      (node (ref "U2") (pin "52") (pinfunction "PE6(T3/INT6)_52") (pintype "bidirectional"))
    )
    (net (code "57") (name "PE7") (class "Default")
      (node (ref "U2") (pin "53") (pinfunction "PE7(ICP3/INT7/CLKO)_53") (pintype "bidirectional"))
    )
    (net (code "58") (name "PG0") (class "Default")
      (node (ref "U2") (pin "14") (pinfunction "PG0(DIG3)_14") (pintype "bidirectional"))
    )
    (net (code "59") (name "PG1") (class "Default")
      (node (ref "U2") (pin "15") (pinfunction "PG1(DIG1)_15") (pintype "bidirectional"))
    )
    (net (code "60") (name "PG2") (class "Default")
      (node (ref "U2") (pin "16") (pinfunction "PG2(AMR)_16") (pintype "bidirectional"))
    )
    (net (code "61") (name "PG5") (class "Default")
      (node (ref "R15") (pin "1") (pinfunction "1_1") (pintype "passive"))
      (node (ref "U2") (pin "19") (pinfunction "PG5(OC0B)_19") (pintype "bidirectional"))
    )
    (net (code "62") (name "RESET") (class "Default")
      (node (ref "C3") (pin "2") (pinfunction "2_2") (pintype "passive"))
      (node (ref "J2") (pin "5") (pinfunction "5_5") (pintype "passive"))
      (node (ref "R5") (pin "1") (pinfunction "1_1") (pintype "passive"))
      (node (ref "SW1") (pin "1") (pinfunction "1_1") (pintype "passive"))
      (node (ref "SW1") (pin "2") (pinfunction "1_2") (pintype "passive"))
      (node (ref "U2") (pin "12") (pinfunction "RSTN_12") (pintype "bidirectional"))
    )
    (net (code "63") (name "RSTON") (class "Default")
      (node (ref "U2") (pin "13") (pinfunction "RSTON_13") (pintype "bidirectional"))
    )
    (net (code "64") (name "RX0") (class "Default")
      (node (ref "FTDI") (pin "TXO") (pinfunction "3_TXO") (pintype "passive"))
      (node (ref "U2") (pin "46") (pinfunction "PE0(RXD0/PCINT8)_46") (pintype "bidirectional"))
    )
    (net (code "65") (name "RX1") (class "Default")
      (node (ref "FTDI_(SERIAL_ONLY)") (pin "TXO") (pinfunction "3_TXO") (pintype "passive"))
      (node (ref "U2") (pin "27") (pinfunction "PD2(RXD1/INT2)_27") (pintype "bidirectional"))
    )
    (net (code "66") (name "SCK") (class "Default")
      (node (ref "J2") (pin "3") (pinfunction "3_3") (pintype "passive"))
      (node (ref "U2") (pin "37") (pinfunction "PB1(SCK/PCINT1)_37") (pintype "bidirectional"))
    )
    (net (code "67") (name "SCL") (class "Default")
      (node (ref "U$1") (pin "P$21") (pinfunction "P$21_SCL/SPC_P$21") (pintype "bidirectional"))
      (node (ref "U2") (pin "25") (pinfunction "PD0(SCL/INT0)_25") (pintype "bidirectional"))
    )
    (net (code "68") (name "SDA") (class "Default")
      (node (ref "U$1") (pin "P$24") (pinfunction "P$24_SDA_P$24") (pintype "bidirectional"))
      (node (ref "U2") (pin "26") (pinfunction "PD1(SDA/INT1)_26") (pintype "bidirectional"))
    )
    (net (code "69") (name "SSN") (class "Default")
      (node (ref "U2") (pin "36") (pinfunction "PB0(SSN/PCINT0)_36") (pintype "bidirectional"))
    )
    (net (code "70") (name "TX0") (class "Default")
      (node (ref "FTDI") (pin "RXI") (pinfunction "2_RXI") (pintype "passive"))
      (node (ref "U2") (pin "47") (pinfunction "PE1(TXD0)_47") (pintype "bidirectional"))
    )
    (net (code "71") (name "TX1") (class "Default")
      (node (ref "FTDI_(SERIAL_ONLY)") (pin "RXI") (pinfunction "2_RXI") (pintype "passive"))
      (node (ref "U2") (pin "28") (pinfunction "PD3(TXD1/INT3)_28") (pintype "bidirectional"))
    )
    (net (code "72") (name "VCC") (class "Default")
      (node (ref "C1") (pin "1") (pinfunction "1_1") (pintype "passive"))
      (node (ref "C12") (pin "1") (pinfunction "1_1") (pintype "passive"))
      (node (ref "C13") (pin "1") (pinfunction "1_1") (pintype "passive"))
      (node (ref "C17") (pin "1") (pinfunction "1_1") (pintype "passive"))
      (node (ref "C35") (pin "1") (pinfunction "1_1") (pintype "passive"))
      (node (ref "C36") (pin "1") (pinfunction "1_1") (pintype "passive"))
      (node (ref "D3") (pin "C") (pinfunction "C_C") (pintype "passive"))
      (node (ref "D4") (pin "C") (pinfunction "C_C") (pintype "passive"))
      (node (ref "D5") (pin "C") (pinfunction "C_C") (pintype "passive"))
      (node (ref "D7") (pin "C") (pinfunction "C_C") (pintype "passive"))
      (node (ref "J4") (pin "2") (pinfunction "2_2") (pintype "passive"))
      (node (ref "PIN_3") (pin "V+") (pinfunction "V+_V+") (pintype "bidirectional"))
      (node (ref "PIN_4") (pin "V+") (pinfunction "V+_V+") (pintype "bidirectional"))
      (node (ref "PIN_5") (pin "V+") (pinfunction "V+_V+") (pintype "bidirectional"))
      (node (ref "PIN_8") (pin "V+") (pinfunction "V+_V+") (pintype "bidirectional"))
      (node (ref "U$2") (pin "1") (pinfunction "IN_1") (pintype "input"))
      (node (ref "U$2") (pin "3") (pinfunction "EN_3") (pintype "input"))
      (node (ref "U$4") (pin "P$1") (pinfunction "1_P$1") (pintype "passive"))
      (node (ref "U$5") (pin "P$1") (pinfunction "1_P$1") (pintype "passive"))
      (node (ref "U$6") (pin "P$1") (pinfunction "1_P$1") (pintype "passive"))
      (node (ref "U$7") (pin "P$1") (pinfunction "1_P$1") (pintype "passive"))
    )
    (net (code "73") (name "unconnected-(FTDI-4-PadVCC)") (class "Default")
      (node (ref "FTDI") (pin "VCC") (pinfunction "4_VCC") (pintype "passive"))
    )
    (net (code "74") (name "unconnected-(FTDI-5-PadCTS)") (class "Default")
      (node (ref "FTDI") (pin "CTS") (pinfunction "5_CTS") (pintype "passive"))
    )
    (net (code "75") (name "unconnected-(FTDI_(SERIAL_ONLY)-1-PadDTR)") (class "Default")
      (node (ref "FTDI_(SERIAL_ONLY)") (pin "DTR") (pinfunction "1_DTR") (pintype "passive"))
    )
    (net (code "76") (name "unconnected-(FTDI_(SERIAL_ONLY)-4-PadVCC)") (class "Default")
      (node (ref "FTDI_(SERIAL_ONLY)") (pin "VCC") (pinfunction "4_VCC") (pintype "passive"))
    )
    (net (code "77") (name "unconnected-(FTDI_(SERIAL_ONLY)-5-PadCTS)") (class "Default")
      (node (ref "FTDI_(SERIAL_ONLY)") (pin "CTS") (pinfunction "5_CTS") (pintype "passive"))
    )
    (net (code "78") (name "unconnected-(J2-Pad2)") (class "Default")
      (node (ref "J2") (pin "2") (pinfunction "2_2") (pintype "passive"))
    )
    (net (code "79") (name "unconnected-(J3-Pad1)") (class "Default")
      (node (ref "J3") (pin "1") (pinfunction "1_1") (pintype "passive"))
    )
    (net (code "80") (name "unconnected-(J3-Pad2)") (class "Default")
      (node (ref "J3") (pin "2") (pinfunction "2_2") (pintype "passive"))
    )
    (net (code "81") (name "unconnected-(J3-Pad3)") (class "Default")
      (node (ref "J3") (pin "3") (pinfunction "3_3") (pintype "passive"))
    )
    (net (code "82") (name "unconnected-(J3-Pad4)") (class "Default")
      (node (ref "J3") (pin "4") (pinfunction "4_4") (pintype "passive"))
    )
    (net (code "83") (name "unconnected-(J3-Pad5)") (class "Default")
      (node (ref "J3") (pin "5") (pinfunction "5_5") (pintype "passive"))
    )
    (net (code "84") (name "unconnected-(J3-Pad6)") (class "Default")
      (node (ref "J3") (pin "6") (pinfunction "6_6") (pintype "passive"))
    )
    (net (code "85") (name "unconnected-(J3-Pad7)") (class "Default")
      (node (ref "J3") (pin "7") (pinfunction "7_7") (pintype "passive"))
    )
    (net (code "86") (name "unconnected-(J3-Pad8)") (class "Default")
      (node (ref "J3") (pin "8") (pinfunction "8_8") (pintype "passive"))
    )
    (net (code "87") (name "unconnected-(J3-Pad9)") (class "Default")
      (node (ref "J3") (pin "9") (pinfunction "9_9") (pintype "passive"))
    )
    (net (code "88") (name "unconnected-(J3-Pad10)") (class "Default")
      (node (ref "J3") (pin "10") (pinfunction "10_10") (pintype "passive"))
    )
    (net (code "89") (name "unconnected-(R16-Pad1)") (class "Default")
      (node (ref "R16") (pin "1") (pinfunction "1_1") (pintype "passive"))
    )
    (net (code "90") (name "unconnected-(U$1-P$1_RES-PadP$1)") (class "Default")
      (node (ref "U$1") (pin "P$1") (pinfunction "P$1_RES_P$1") (pintype "bidirectional"))
    )
    (net (code "91") (name "unconnected-(U$1-P$10_DEN_G-PadP$10)") (class "Default")
      (node (ref "U$1") (pin "P$10") (pinfunction "P$10_DEN_G_P$10") (pintype "bidirectional"))
    )
    (net (code "92") (name "unconnected-(U$1-P$11_INT_G-PadP$11)") (class "Default")
      (node (ref "U$1") (pin "P$11") (pinfunction "P$11_INT_G_P$11") (pintype "bidirectional"))
    )
    (net (code "93") (name "unconnected-(U$1-P$12_DADY_G-PadP$12)") (class "Default")
      (node (ref "U$1") (pin "P$12") (pinfunction "P$12_DADY_G_P$12") (pintype "bidirectional"))
    )
    (net (code "94") (name "unconnected-(U$1-P$13_INT1_XM-PadP$13)") (class "Default")
      (node (ref "U$1") (pin "P$13") (pinfunction "P$13_INT1_XM_P$13") (pintype "bidirectional"))
    )
    (net (code "95") (name "unconnected-(U$1-P$14_INT2_XM-PadP$14)") (class "Default")
      (node (ref "U$1") (pin "P$14") (pinfunction "P$14_INT2_XM_P$14") (pintype "bidirectional"))
    )
    (net (code "96") (name "unconnected-(U2-PG3(TOSC2)-Pad17)") (class "Default")
      (node (ref "U2") (pin "17") (pinfunction "PG3(TOSC2)_17") (pintype "bidirectional"))
    )
    (net (code "97") (name "unconnected-(U2-PG4(TOSC1)-Pad18)") (class "Default")
      (node (ref "U2") (pin "18") (pinfunction "PG4(TOSC1)_18") (pintype "bidirectional"))
    )
  )
)
